# control.net
KiCad netlist of a schematic drawn in EAGLE
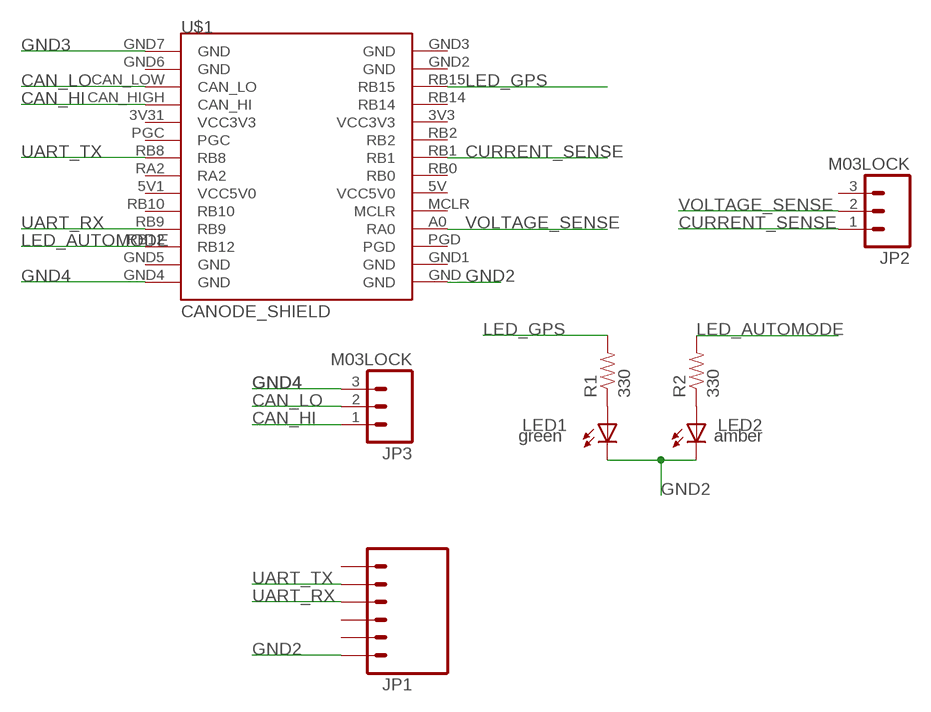
[diagram p0: schematic, sheet 1]

(export (version "E")
  (design (tool "Eeschema 10.0.6"))
  (components
    (comp (ref "JP1")
      (value "M06LOCK")
      (footprint "eagle-import:1X06_LOCK")
      (libsource (lib "eagle-import") (part "M06LOCK"))
    )
    (comp (ref "JP2")
      (value "M03LOCK")
      (footprint "eagle-import:1X03_LOCK")
      (libsource (lib "eagle-import") (part "M03LOCK"))
    )
    (comp (ref "JP3")
      (value "M03LOCK")
      (footprint "eagle-import:1X03_LOCK")
      (libsource (lib "eagle-import") (part "M03LOCK"))
    )
    (comp (ref "LED1")
      (value "LED1206")
      (footprint "eagle-import:LED-1206")
      (fields (field (name "COLOR") "green"))
      (libsource (lib "eagle-import") (part "LED1206"))
    )
    (comp (ref "LED2")
      (value "LED1206")
      (footprint "eagle-import:LED-1206")
      (fields (field (name "COLOR") "amber"))
      (libsource (lib "eagle-import") (part "LED1206"))
    )
    (comp (ref "R1")
      (value "330")
      (footprint "eagle-import:0805")
      (libsource (lib "eagle-import") (part "RESISTOR0805-RES"))
    )
    (comp (ref "R2")
      (value "330")
      (footprint "eagle-import:0805")
      (libsource (lib "eagle-import") (part "RESISTOR0805-RES"))
    )
    (comp (ref "U$1")
      (value "CANODE_SHIELD")
      (footprint "eagle-import:CANODE_SHIELD")
      (libsource (lib "eagle-import") (part "CANODE_SHIELD"))
    )
  )
  (nets
    (net (code "1") (name "/CAN_HI") (class "Default")
      (node (ref "JP3") (pin "1") (pinfunction "1_1") (pintype "passive"))
      (node (ref "U$1") (pin "CAN_HIGH") (pinfunction "CAN_HI_CAN_HIGH") (pintype "bidirectional"))
    )
    (net (code "2") (name "/CAN_LO") (class "Default")
      (node (ref "JP3") (pin "2") (pinfunction "2_2") (pintype "passive"))
      (node (ref "U$1") (pin "CAN_LOW") (pinfunction "CAN_LO_CAN_LOW") (pintype "bidirectional"))
    )
    (net (code "3") (name "/CURRENT_SENSE") (class "Default")
      (node (ref "JP2") (pin "1") (pinfunction "1_1") (pintype "passive"))
      (node (ref "U$1") (pin "RB1") (pinfunction "RB1_RB1") (pintype "bidirectional"))
    )
    (net (code "4") (name "/GND2") (class "Default")
      (node (ref "JP1") (pin "1") (pinfunction "1_1") (pintype "passive"))
      (node (ref "LED1") (pin "C") (pinfunction "C_C") (pintype "passive"))
      (node (ref "LED2") (pin "C") (pinfunction "C_C") (pintype "passive"))
      (node (ref "U$1") (pin "GND") (pinfunction "GND_GND") (pintype "bidirectional"))
    )
    (net (code "5") (name "/GND3") (class "Default")
      (node (ref "U$1") (pin "GND7") (pinfunction "GND_GND7") (pintype "bidirectional"))
    )
    (net (code "6") (name "/GND4") (class "Default")
      (node (ref "JP3") (pin "3") (pinfunction "3_3") (pintype "passive"))
      (node (ref "U$1") (pin "GND4") (pinfunction "GND_GND4") (pintype "bidirectional"))
    )
    (net (code "7") (name "/LED_AUTOMODE") (class "Default")
      (node (ref "R2") (pin "2") (pinfunction "2_2") (pintype "passive"))
      (node (ref "U$1") (pin "RB12") (pinfunction "RB12_RB12") (pintype "bidirectional"))
    )
    (net (code "8") (name "/LED_GPS") (class "Default")
      (node (ref "R1") (pin "2") (pinfunction "2_2") (pintype "passive"))
      (node (ref "U$1") (pin "RB15") (pinfunction "RB15_RB15") (pintype "bidirectional"))
    )
    (net (code "9") (name "/UART_RX") (class "Default")
      (node (ref "JP1") (pin "4") (pinfunction "4_4") (pintype "passive"))
      (node (ref "U$1") (pin "RB9") (pinfunction "RB9_RB9") (pintype "bidirectional"))
    )
    (net (code "10") (name "/UART_TX") (class "Default")
      (node (ref "JP1") (pin "5") (pinfunction "5_5") (pintype "passive"))
      (node (ref "U$1") (pin "RB8") (pinfunction "RB8_RB8") (pintype "bidirectional"))
    )
    (net (code "11") (name "/VOLTAGE_SENSE") (class "Default")
      (node (ref "JP2") (pin "2") (pinfunction "2_2") (pintype "passive"))
      (node (ref "U$1") (pin "A0") (pinfunction "RA0_A0") (pintype "bidirectional"))
    )
    (net (code "12") (name "Net-(LED1-PadA)") (class "Default")
      (node (ref "LED1") (pin "A") (pinfunction "A_A") (pintype "passive"))
      (node (ref "R1") (pin "1") (pinfunction "1_1") (pintype "passive"))
    )
    (net (code "13") (name "Net-(LED2-PadA)") (class "Default")
      (node (ref "LED2") (pin "A") (pinfunction "A_A") (pintype "passive"))
      (node (ref "R2") (pin "1") (pinfunction "1_1") (pintype "passive"))
    )
    (net (code "14") (name "unconnected-(JP1-Pad2)") (class "Default")
      (node (ref "JP1") (pin "2") (pinfunction "2_2") (pintype "passive"))
    )
    (net (code "15") (name "unconnected-(JP1-Pad3)") (class "Default")
      (node (ref "JP1") (pin "3") (pinfunction "3_3") (pintype "passive"))
    )
    (net (code "16") (name "unconnected-(JP1-Pad6)") (class "Default")
      (node (ref "JP1") (pin "6") (pinfunction "6_6") (pintype "passive"))
    )
    (net (code "17") (name "unconnected-(JP2-Pad3)") (class "Default")
      (node (ref "JP2") (pin "3") (pinfunction "3_3") (pintype "passive"))
    )
    (net (code "18") (name "unconnected-(U$1-GND-PadGND1)") (class "Default")
      (node (ref "U$1") (pin "GND1") (pinfunction "GND_GND1") (pintype "bidirectional"))
    )
    (net (code "19") (name "unconnected-(U$1-GND-PadGND2)") (class "Default")
      (node (ref "U$1") (pin "GND2") (pinfunction "GND_GND2") (pintype "bidirectional"))
    )
    (net (code "20") (name "unconnected-(U$1-GND-PadGND3)") (class "Default")
      (node (ref "U$1") (pin "GND3") (pinfunction "GND_GND3") (pintype "bidirectional"))
    )
    (net (code "21") (name "unconnected-(U$1-GND-PadGND5)") (class "Default")
      (node (ref "U$1") (pin "GND5") (pinfunction "GND_GND5") (pintype "bidirectional"))
    )
    (net (code "22") (name "unconnected-(U$1-GND-PadGND6)") (class "Default")
      (node (ref "U$1") (pin "GND6") (pinfunction "GND_GND6") (pintype "bidirectional"))
    )
    (net (code "23") (name "unconnected-(U$1-PadMCLR)") (class "Default")
      (node (ref "U$1") (pin "MCLR") (pinfunction "MCLR_MCLR") (pintype "bidirectional"))
    )
    (net (code "24") (name "unconnected-(U$1-PadPGC)") (class "Default")
      (node (ref "U$1") (pin "PGC") (pinfunction "PGC_PGC") (pintype "bidirectional"))
    )
    (net (code "25") (name "unconnected-(U$1-PadPGD)") (class "Default")
      (node (ref "U$1") (pin "PGD") (pinfunction "PGD_PGD") (pintype "bidirectional"))
    )
    (net (code "26") (name "unconnected-(U$1-PadRA2)") (class "Default")
      (node (ref "U$1") (pin "RA2") (pinfunction "RA2_RA2") (pintype "bidirectional"))
    )
    (net (code "27") (name "unconnected-(U$1-PadRB0)") (class "Default")
      (node (ref "U$1") (pin "RB0") (pinfunction "RB0_RB0") (pintype "bidirectional"))
    )
    (net (code "28") (name "unconnected-(U$1-PadRB2)") (class "Default")
      (node (ref "U$1") (pin "RB2") (pinfunction "RB2_RB2") (pintype "bidirectional"))
    )
    (net (code "29") (name "unconnected-(U$1-PadRB10)") (class "Default")
      (node (ref "U$1") (pin "RB10") (pinfunction "RB10_RB10") (pintype "bidirectional"))
    )
    (net (code "30") (name "unconnected-(U$1-PadRB14)") (class "Default")
      (node (ref "U$1") (pin "RB14") (pinfunction "RB14_RB14") (pintype "bidirectional"))
    )
    (net (code "31") (name "unconnected-(U$1-VCC3V3-Pad3V3)") (class "Default")
      (node (ref "U$1") (pin "3V3") (pinfunction "VCC3V3_3V3") (pintype "bidirectional"))
    )
    (net (code "32") (name "unconnected-(U$1-VCC3V3-Pad3V31)") (class "Default")
      (node (ref "U$1") (pin "3V31") (pinfunction "VCC3V3_3V31") (pintype "bidirectional"))
    )
    (net (code "33") (name "unconnected-(U$1-VCC5V0-Pad5V)") (class "Default")
      (node (ref "U$1") (pin "5V") (pinfunction "VCC5V0_5V") (pintype "bidirectional"))
    )
    (net (code "34") (name "unconnected-(U$1-VCC5V0-Pad5V1)") (class "Default")
      (node (ref "U$1") (pin "5V1") (pinfunction "VCC5V0_5V1") (pintype "bidirectional"))
    )
  )
)
